# EspHeatController_v1_0_Eagle9x.net
KiCad netlist of a schematic drawn in EAGLE
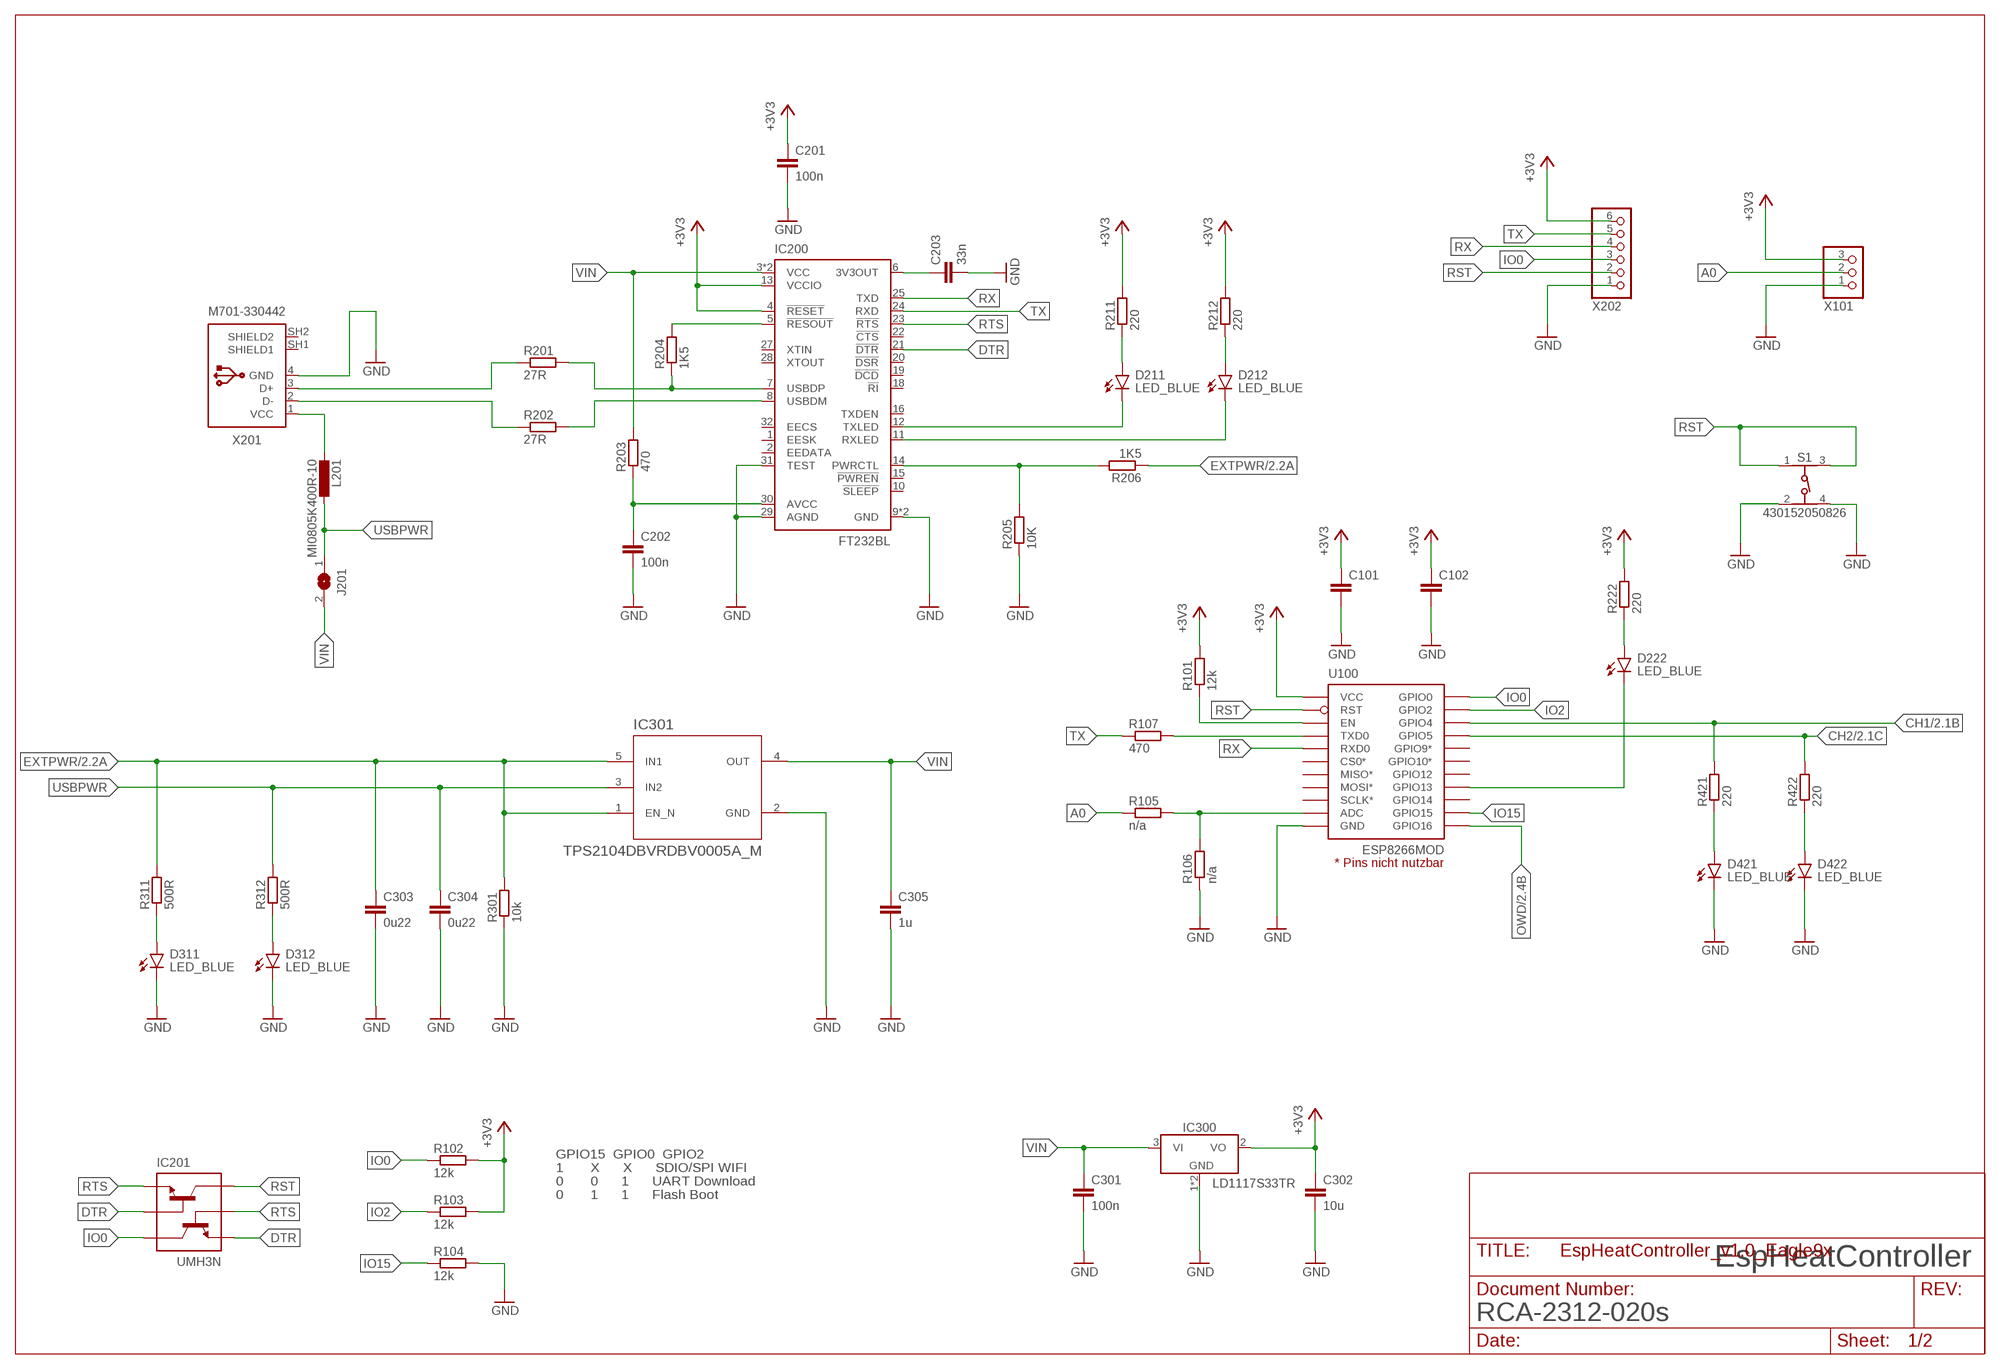
[diagram p0: schematic, sheet 1]
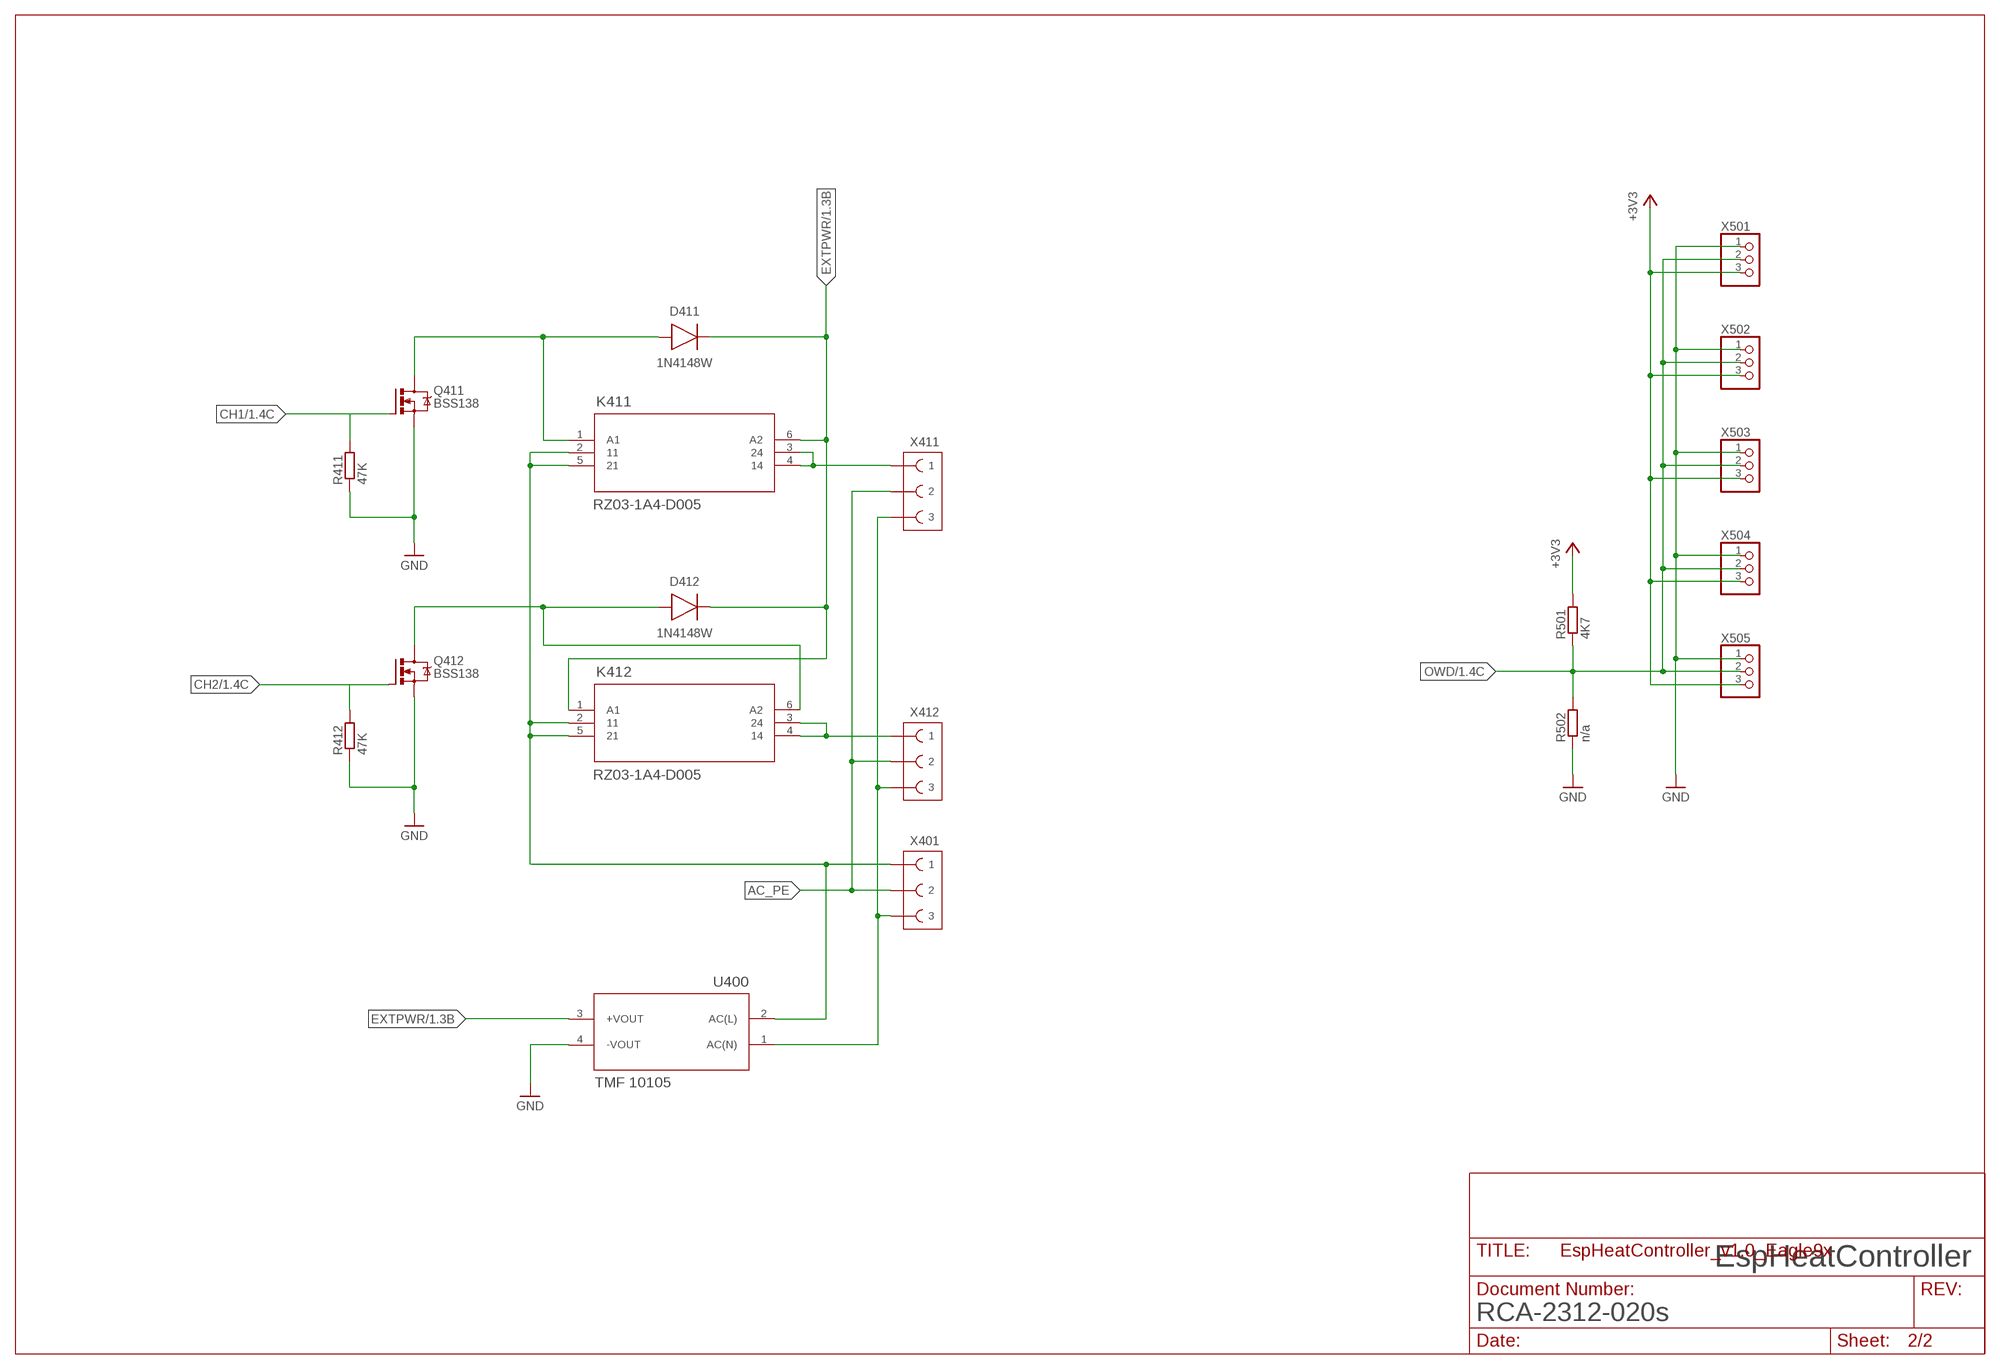
[diagram p1: schematic, sheet 2]

(export (version "E")
  (design (tool "Eeschema 10.0.6"))
  (components
    (comp (ref "C101")
      (value "C-EUC0805")
      (footprint "eagle-import:C0805")
      (libsource (lib "eagle-import") (part "C-EUC0805"))
    )
    (comp (ref "C102")
      (value "C-EUC0805")
      (footprint "eagle-import:C0805")
      (libsource (lib "eagle-import") (part "C-EUC0805"))
    )
    (comp (ref "C201")
      (value "100n")
      (footprint "eagle-import:C0805")
      (libsource (lib "eagle-import") (part "C-EUC0805"))
    )
    (comp (ref "C202")
      (value "100n")
      (footprint "eagle-import:C0805")
      (libsource (lib "eagle-import") (part "C-EUC0805"))
    )
    (comp (ref "C203")
      (value "33n")
      (footprint "eagle-import:C0805")
      (libsource (lib "eagle-import") (part "C-EUC0805"))
    )
    (comp (ref "C301")
      (value "100n")
      (footprint "eagle-import:C0805")
      (libsource (lib "eagle-import") (part "C-EUC0805"))
    )
    (comp (ref "C302")
      (value "10u")
      (footprint "eagle-import:C0805")
      (libsource (lib "eagle-import") (part "C-EUC0805"))
    )
    (comp (ref "C303")
      (value "0u22")
      (footprint "eagle-import:C0805")
      (libsource (lib "eagle-import") (part "C-EUC0805"))
    )
    (comp (ref "C304")
      (value "0u22")
      (footprint "eagle-import:C0805")
      (libsource (lib "eagle-import") (part "C-EUC0805"))
    )
    (comp (ref "C305")
      (value "1u")
      (footprint "eagle-import:C0805")
      (libsource (lib "eagle-import") (part "C-EUC0805"))
    )
    (comp (ref "D211")
      (value "LED_BLUE")
      (footprint "eagle-import:LEDC2012X110N_FLAT-B")
      (libsource (lib "eagle-import") (part "CHIP-FLAT-B_0805"))
    )
    (comp (ref "D212")
      (value "LED_BLUE")
      (footprint "eagle-import:LEDC2012X110N_FLAT-B")
      (libsource (lib "eagle-import") (part "CHIP-FLAT-B_0805"))
    )
    (comp (ref "D222")
      (value "LED_BLUE")
      (footprint "eagle-import:LEDC2012X110N_FLAT-B")
      (libsource (lib "eagle-import") (part "CHIP-FLAT-B_0805"))
    )
    (comp (ref "D311")
      (value "LED_BLUE")
      (footprint "eagle-import:LEDC2012X110N_FLAT-B")
      (libsource (lib "eagle-import") (part "CHIP-FLAT-B_0805"))
    )
    (comp (ref "D312")
      (value "LED_BLUE")
      (footprint "eagle-import:LEDC2012X110N_FLAT-B")
      (libsource (lib "eagle-import") (part "CHIP-FLAT-B_0805"))
    )
    (comp (ref "D421")
      (value "LED_BLUE")
      (footprint "eagle-import:LEDC2012X110N_FLAT-B")
      (libsource (lib "eagle-import") (part "CHIP-FLAT-B_0805"))
    )
    (comp (ref "D422")
      (value "LED_BLUE")
      (footprint "eagle-import:LEDC2012X110N_FLAT-B")
      (libsource (lib "eagle-import") (part "CHIP-FLAT-B_0805"))
    )
    (comp (ref "IC200")
      (value "FT232BL")
      (footprint "eagle-import:LQFP32-7X7")
      (fields (field (name "MF") "FARNELL") (field (name "MPN") "FT232BL/TR"))
      (libsource (lib "eagle-import") (part "FT232BL"))
    )
    (comp (ref "IC201")
      (value "UMH3N")
      (footprint "eagle-import:SOT-363_ROM")
      (fields
        (field (name "MANUFACTURER_PART_NUMBER") "UMH3NTN")
        (field (name "COPYRIGHT") "Copyright (C) 2023 Ultra Librarian. All rights reserved.")
      )
      (libsource (lib "eagle-import") (part "UMH3NTNSOT-363_ROM"))
    )
    (comp (ref "IC300")
      (value "LD1117S33TR")
      (footprint "eagle-import:SOT230P700X170-4")
      (fields (field (name "MANUFACTURER") "STMicroelectronics") (field (name "MPN") "Generic"))
      (libsource (lib "eagle-import") (part "LD1117_SOT223"))
    )
    (comp (ref "IC301")
      (value "TPS2104DBVRDBV0005A_M")
      (footprint "eagle-import:DBV0005A_M")
      (fields
        (field (name "MANUFACTURER_PART_NUMBER") "TPS2104DBVR")
        (field (name "COPYRIGHT") "Copyright (C) 2023 Ultra Librarian. All rights reserved.")
      )
      (libsource (lib "eagle-import") (part "TPS2104DBVRDBV0005A_M"))
    )
    (comp (ref "J201")
      (value "SJ")
      (footprint "eagle-import:SJ")
      (libsource (lib "eagle-import") (part "SJ"))
    )
    (comp (ref "L201")
      (value "MI0805K400R-10")
      (footprint "eagle-import:L2012C")
      (libsource (lib "eagle-import") (part "L-EUL2012C"))
    )
    (comp (ref "R101")
      (value "12k")
      (footprint "eagle-import:R0603")
      (libsource (lib "eagle-import") (part "R-EU_R0603"))
    )
    (comp (ref "R102")
      (value "12k")
      (footprint "eagle-import:R0603")
      (libsource (lib "eagle-import") (part "R-EU_R0603"))
    )
    (comp (ref "R103")
      (value "12k")
      (footprint "eagle-import:R0603")
      (libsource (lib "eagle-import") (part "R-EU_R0603"))
    )
    (comp (ref "R104")
      (value "12k")
      (footprint "eagle-import:R0603")
      (libsource (lib "eagle-import") (part "R-EU_R0603"))
    )
    (comp (ref "R105")
      (value "n/a")
      (footprint "eagle-import:R0603")
      (libsource (lib "eagle-import") (part "R-EU_R0603"))
    )
    (comp (ref "R106")
      (value "n/a")
      (footprint "eagle-import:R0603")
      (libsource (lib "eagle-import") (part "R-EU_R0603"))
    )
    (comp (ref "R107")
      (value "470")
      (footprint "eagle-import:R0603")
      (libsource (lib "eagle-import") (part "R-EU_R0603"))
    )
    (comp (ref "R201")
      (value "27R")
      (footprint "eagle-import:R0603")
      (libsource (lib "eagle-import") (part "R-EU_R0603"))
    )
    (comp (ref "R202")
      (value "27R")
      (footprint "eagle-import:R0603")
      (libsource (lib "eagle-import") (part "R-EU_R0603"))
    )
    (comp (ref "R203")
      (value "470")
      (footprint "eagle-import:R0603")
      (libsource (lib "eagle-import") (part "R-EU_R0603"))
    )
    (comp (ref "R204")
      (value "1K5")
      (footprint "eagle-import:R0603")
      (libsource (lib "eagle-import") (part "R-EU_R0603"))
    )
    (comp (ref "R205")
      (value "10K")
      (footprint "eagle-import:R0603")
      (libsource (lib "eagle-import") (part "R-EU_R0603"))
    )
    (comp (ref "R206")
      (value "1K5")
      (footprint "eagle-import:R0603")
      (libsource (lib "eagle-import") (part "R-EU_R0603"))
    )
    (comp (ref "R211")
      (value "220")
      (footprint "eagle-import:R0603")
      (libsource (lib "eagle-import") (part "R-EU_R0603"))
    )
    (comp (ref "R212")
      (value "220")
      (footprint "eagle-import:R0603")
      (libsource (lib "eagle-import") (part "R-EU_R0603"))
    )
    (comp (ref "R222")
      (value "220")
      (footprint "eagle-import:R0603")
      (libsource (lib "eagle-import") (part "R-EU_R0603"))
    )
    (comp (ref "R301")
      (value "10k")
      (footprint "eagle-import:R0603")
      (libsource (lib "eagle-import") (part "R-EU_R0603"))
    )
    (comp (ref "R311")
      (value "500R")
      (footprint "eagle-import:R0603")
      (libsource (lib "eagle-import") (part "R-EU_R0603"))
    )
    (comp (ref "R312")
      (value "500R")
      (footprint "eagle-import:R0603")
      (libsource (lib "eagle-import") (part "R-EU_R0603"))
    )
    (comp (ref "R421")
      (value "220")
      (footprint "eagle-import:R0603")
      (libsource (lib "eagle-import") (part "R-EU_R0603"))
    )
    (comp (ref "R422")
      (value "220")
      (footprint "eagle-import:R0603")
      (libsource (lib "eagle-import") (part "R-EU_R0603"))
    )
    (comp (ref "S1")
      (value "430152050826")
      (footprint "eagle-import:430152050826")
      (libsource (lib "eagle-import") (part "430152050826"))
    )
    (comp (ref "U100")
      (value "ESP8266MOD")
      (footprint "eagle-import:ESP12F-SMD")
      (libsource (lib "eagle-import") (part "ESP8266MOD"))
    )
    (comp (ref "X101")
      (value "PINHD-1X3")
      (footprint "eagle-import:1X03")
      (libsource (lib "eagle-import") (part "PINHD-1X3"))
    )
    (comp (ref "X201")
      (value "M701-330442")
      (footprint "eagle-import:M701-330442")
      (fields (field (name "MANUFACTURER") "Harwin"))
      (libsource (lib "eagle-import") (part "M701-330442"))
    )
    (comp (ref "X202")
      (value "PINHD-1X6")
      (footprint "eagle-import:1X06")
      (libsource (lib "eagle-import") (part "PINHD-1X6"))
    )
    (comp (ref "D411")
      (value "1N4148W")
      (footprint "eagle-import:SOD3715X135")
      (fields (field (name "MANUFACTURER") "Diodes Incorporated"))
      (libsource (lib "eagle-import") (part "DIODE__SOD123G1N4148W-7-F"))
    )
    (comp (ref "D412")
      (value "1N4148W")
      (footprint "eagle-import:SOD3715X135")
      (fields (field (name "MANUFACTURER") "Diodes Incorporated"))
      (libsource (lib "eagle-import") (part "DIODE__SOD123G1N4148W-7-F"))
    )
    (comp (ref "K411")
      (value "RZ03-1A4-D005")
      (footprint "eagle-import:RELAY-SPST2_5MM")
      (fields
        (field (name "MANUFACTURER_PART_NUMBER") "1-1415899-6")
        (field (name "COPYRIGHT") "Copyright (C) 2016 Accelerated Designs. All rights reserved")
      )
      (libsource (lib "eagle-import") (part "1-1415899-6"))
    )
    (comp (ref "K412")
      (value "RZ03-1A4-D005")
      (footprint "eagle-import:RELAY-SPST2_5MM")
      (fields
        (field (name "MANUFACTURER_PART_NUMBER") "1-1415899-6")
        (field (name "COPYRIGHT") "Copyright (C) 2016 Accelerated Designs. All rights reserved")
      )
      (libsource (lib "eagle-import") (part "1-1415899-6"))
    )
    (comp (ref "Q411")
      (value "BSS138")
      (footprint "eagle-import:SOT23")
      (libsource (lib "eagle-import") (part "NMOSFETSOT23-GSD"))
    )
    (comp (ref "Q412")
      (value "BSS138")
      (footprint "eagle-import:SOT23")
      (libsource (lib "eagle-import") (part "NMOSFETSOT23-GSD"))
    )
    (comp (ref "R411")
      (value "47K")
      (footprint "eagle-import:R0805W")
      (libsource (lib "eagle-import") (part "R-EU_R0805W"))
    )
    (comp (ref "R412")
      (value "47K")
      (footprint "eagle-import:R0805W")
      (libsource (lib "eagle-import") (part "R-EU_R0805W"))
    )
    (comp (ref "R501")
      (value "4K7")
      (footprint "eagle-import:R0805W")
      (libsource (lib "eagle-import") (part "R-EU_R0805W"))
    )
    (comp (ref "R502")
      (value "n/a")
      (footprint "eagle-import:R0805W")
      (libsource (lib "eagle-import") (part "R-EU_R0805W"))
    )
    (comp (ref "U400")
      (value "TMF 10105")
      (footprint "eagle-import:TMF10")
      (libsource (lib "eagle-import") (part "TMF_101"))
    )
    (comp (ref "X401")
      (value "SPT2,5/3-V-5,0")
      (footprint "eagle-import:SPT2,5_3-V-5,0")
      (fields (field (name "ARROW_PART_NUMBER") "1991105") (field (name "MOUSER_PART_NUMBER") "651-1991105"))
      (libsource (lib "eagle-import") (part "SPT2,5/3-V-5,0"))
    )
    (comp (ref "X411")
      (value "SPT2,5/3-V-5,0")
      (footprint "eagle-import:SPT2,5_3-V-5,0")
      (fields (field (name "ARROW_PART_NUMBER") "1991105") (field (name "MOUSER_PART_NUMBER") "651-1991105"))
      (libsource (lib "eagle-import") (part "SPT2,5/3-V-5,0"))
    )
    (comp (ref "X412")
      (value "SPT2,5/3-V-5,0")
      (footprint "eagle-import:SPT2,5_3-V-5,0")
      (fields (field (name "ARROW_PART_NUMBER") "1991105") (field (name "MOUSER_PART_NUMBER") "651-1991105"))
      (libsource (lib "eagle-import") (part "SPT2,5/3-V-5,0"))
    )
    (comp (ref "X501")
      (value "PINHD-1X3")
      (footprint "eagle-import:1X03")
      (libsource (lib "eagle-import") (part "PINHD-1X3"))
    )
    (comp (ref "X502")
      (value "PINHD-1X3")
      (footprint "eagle-import:1X03")
      (libsource (lib "eagle-import") (part "PINHD-1X3"))
    )
    (comp (ref "X503")
      (value "PINHD-1X3")
      (footprint "eagle-import:1X03")
      (libsource (lib "eagle-import") (part "PINHD-1X3"))
    )
    (comp (ref "X504")
      (value "PINHD-1X3")
      (footprint "eagle-import:1X03")
      (libsource (lib "eagle-import") (part "PINHD-1X3"))
    )
    (comp (ref "X505")
      (value "PINHD-1X3")
      (footprint "eagle-import:1X03")
      (libsource (lib "eagle-import") (part "PINHD-1X3"))
    )
  )
  (nets
    (net (code "1") (name "+3V3") (class "Default")
      (node (ref "C101") (pin "1") (pinfunction "1_1") (pintype "passive"))
      (node (ref "C102") (pin "1") (pinfunction "1_1") (pintype "passive"))
      (node (ref "C201") (pin "1") (pinfunction "1_1") (pintype "passive"))
      (node (ref "C302") (pin "1") (pinfunction "1_1") (pintype "passive"))
      (node (ref "IC200") (pin "13") (pinfunction "VCCIO_13") (pintype "power_in"))
      (node (ref "IC200") (pin "4") (pinfunction "~{RESET}_4") (pintype "input"))
      (node (ref "IC300") (pin "2") (pinfunction "VO_2") (pintype "output"))
      (node (ref "R101") (pin "2") (pinfunction "2_2") (pintype "passive"))
      (node (ref "R102") (pin "2") (pinfunction "2_2") (pintype "passive"))
      (node (ref "R103") (pin "2") (pinfunction "2_2") (pintype "passive"))
      (node (ref "R211") (pin "2") (pinfunction "2_2") (pintype "passive"))
      (node (ref "R212") (pin "2") (pinfunction "2_2") (pintype "passive"))
      (node (ref "R222") (pin "2") (pinfunction "2_2") (pintype "passive"))
      (node (ref "R501") (pin "2") (pinfunction "2_2") (pintype "passive"))
      (node (ref "U100") (pin "VCC") (pinfunction "VCC_VCC") (pintype "bidirectional"))
      (node (ref "X101") (pin "3") (pinfunction "3_3") (pintype "passive"))
      (node (ref "X202") (pin "6") (pinfunction "6_6") (pintype "passive"))
      (node (ref "X501") (pin "3") (pinfunction "3_3") (pintype "passive"))
      (node (ref "X502") (pin "3") (pinfunction "3_3") (pintype "passive"))
      (node (ref "X503") (pin "3") (pinfunction "3_3") (pintype "passive"))
      (node (ref "X504") (pin "3") (pinfunction "3_3") (pintype "passive"))
      (node (ref "X505") (pin "3") (pinfunction "3_3") (pintype "passive"))
    )
    (net (code "2") (name "A0") (class "Default")
      (node (ref "R105") (pin "1") (pinfunction "1_1") (pintype "passive"))
      (node (ref "X101") (pin "2") (pinfunction "2_2") (pintype "passive"))
    )
    (net (code "3") (name "AC_PE") (class "Default")
      (node (ref "X401") (pin "2A") (pinfunction "2_2A") (pintype "bidirectional"))
      (node (ref "X401") (pin "2B") (pinfunction "2_2B") (pintype "bidirectional"))
      (node (ref "X411") (pin "2A") (pinfunction "2_2A") (pintype "bidirectional"))
      (node (ref "X411") (pin "2B") (pinfunction "2_2B") (pintype "bidirectional"))
      (node (ref "X412") (pin "2A") (pinfunction "2_2A") (pintype "bidirectional"))
      (node (ref "X412") (pin "2B") (pinfunction "2_2B") (pintype "bidirectional"))
    )
    (net (code "4") (name "CH1") (class "Default")
      (node (ref "Q411") (pin "1") (pinfunction "G_1") (pintype "passive"))
      (node (ref "R411") (pin "2") (pinfunction "2_2") (pintype "passive"))
      (node (ref "R421") (pin "2") (pinfunction "2_2") (pintype "passive"))
      (node (ref "U100") (pin "GPIO4") (pinfunction "GPIO4_GPIO4") (pintype "bidirectional"))
    )
    (net (code "5") (name "CH2") (class "Default")
      (node (ref "Q412") (pin "1") (pinfunction "G_1") (pintype "passive"))
      (node (ref "R412") (pin "2") (pinfunction "2_2") (pintype "passive"))
      (node (ref "R422") (pin "2") (pinfunction "2_2") (pintype "passive"))
      (node (ref "U100") (pin "GPIO5") (pinfunction "GPIO5_GPIO5") (pintype "bidirectional"))
    )
    (net (code "6") (name "DTR") (class "Default")
      (node (ref "IC200") (pin "21") (pinfunction "~{DTR}_21") (pintype "output"))
      (node (ref "IC201") (pin "2") (pinfunction "B1_2") (pintype "passive"))
      (node (ref "IC201") (pin "4") (pinfunction "E2_4") (pintype "passive"))
    )
    (net (code "7") (name "EXTPWR") (class "Default")
      (node (ref "C303") (pin "1") (pinfunction "1_1") (pintype "passive"))
      (node (ref "D411") (pin "1") (pinfunction "C_1") (pintype "passive"))
      (node (ref "D412") (pin "1") (pinfunction "C_1") (pintype "passive"))
      (node (ref "IC301") (pin "1") (pinfunction "EN_N_1") (pintype "input"))
      (node (ref "IC301") (pin "5") (pinfunction "IN1_5") (pintype "input"))
      (node (ref "K411") (pin "6") (pinfunction "A2_6") (pintype "passive"))
      (node (ref "K412") (pin "1") (pinfunction "A1_1") (pintype "passive"))
      (node (ref "R206") (pin "1") (pinfunction "1_1") (pintype "passive"))
      (node (ref "R301") (pin "2") (pinfunction "2_2") (pintype "passive"))
      (node (ref "R311") (pin "2") (pinfunction "2_2") (pintype "passive"))
      (node (ref "U400") (pin "3") (pinfunction "+VOUT_3") (pintype "power_in"))
    )
    (net (code "8") (name "GND") (class "Default")
      (node (ref "C101") (pin "2") (pinfunction "2_2") (pintype "passive"))
      (node (ref "C102") (pin "2") (pinfunction "2_2") (pintype "passive"))
      (node (ref "C201") (pin "2") (pinfunction "2_2") (pintype "passive"))
      (node (ref "C202") (pin "2") (pinfunction "2_2") (pintype "passive"))
      (node (ref "C203") (pin "2") (pinfunction "2_2") (pintype "passive"))
      (node (ref "C301") (pin "2") (pinfunction "2_2") (pintype "passive"))
      (node (ref "C302") (pin "2") (pinfunction "2_2") (pintype "passive"))
      (node (ref "C303") (pin "2") (pinfunction "2_2") (pintype "passive"))
      (node (ref "C304") (pin "2") (pinfunction "2_2") (pintype "passive"))
      (node (ref "C305") (pin "2") (pinfunction "2_2") (pintype "passive"))
      (node (ref "D311") (pin "C") (pinfunction "C_C") (pintype "passive"))
      (node (ref "D312") (pin "C") (pinfunction "C_C") (pintype "passive"))
      (node (ref "D421") (pin "C") (pinfunction "C_C") (pintype "passive"))
      (node (ref "D422") (pin "C") (pinfunction "C_C") (pintype "passive"))
      (node (ref "IC200") (pin "17") (pinfunction "GND_17") (pintype "power_in"))
      (node (ref "IC200") (pin "29") (pinfunction "AGND_29") (pintype "power_in"))
      (node (ref "IC200") (pin "31") (pinfunction "TEST_31") (pintype "input"))
      (node (ref "IC200") (pin "9") (pinfunction "GND_9") (pintype "power_in"))
      (node (ref "IC300") (pin "1") (pinfunction "GND_1") (pintype "passive"))
      (node (ref "IC300") (pin "4") (pinfunction "GND_4") (pintype "passive"))
      (node (ref "IC301") (pin "2") (pinfunction "GND_2") (pintype "power_in"))
      (node (ref "Q411") (pin "2") (pinfunction "S_2") (pintype "passive"))
      (node (ref "Q412") (pin "2") (pinfunction "S_2") (pintype "passive"))
      (node (ref "R104") (pin "2") (pinfunction "2_2") (pintype "passive"))
      (node (ref "R106") (pin "1") (pinfunction "1_1") (pintype "passive"))
      (node (ref "R205") (pin "1") (pinfunction "1_1") (pintype "passive"))
      (node (ref "R301") (pin "1") (pinfunction "1_1") (pintype "passive"))
      (node (ref "R411") (pin "1") (pinfunction "1_1") (pintype "passive"))
      (node (ref "R412") (pin "1") (pinfunction "1_1") (pintype "passive"))
      (node (ref "R502") (pin "1") (pinfunction "1_1") (pintype "passive"))
      (node (ref "S1") (pin "2") (pinfunction "2_2") (pintype "passive"))
      (node (ref "S1") (pin "4") (pinfunction "4_4") (pintype "passive"))
      (node (ref "U100") (pin "GND") (pinfunction "GND_GND") (pintype "bidirectional"))
      (node (ref "U400") (pin "4") (pinfunction "-VOUT_4") (pintype "power_in"))
      (node (ref "X101") (pin "1") (pinfunction "1_1") (pintype "passive"))
      (node (ref "X201") (pin "4") (pinfunction "GND_4") (pintype "power_in"))
      (node (ref "X202") (pin "1") (pinfunction "1_1") (pintype "passive"))
      (node (ref "X501") (pin "1") (pinfunction "1_1") (pintype "passive"))
      (node (ref "X502") (pin "1") (pinfunction "1_1") (pintype "passive"))
      (node (ref "X503") (pin "1") (pinfunction "1_1") (pintype "passive"))
      (node (ref "X504") (pin "1") (pinfunction "1_1") (pintype "passive"))
      (node (ref "X505") (pin "1") (pinfunction "1_1") (pintype "passive"))
    )
    (net (code "9") (name "IO0") (class "Default")
      (node (ref "IC201") (pin "3") (pinfunction "C2_3") (pintype "passive"))
      (node (ref "R102") (pin "1") (pinfunction "1_1") (pintype "passive"))
      (node (ref "U100") (pin "GPIO0") (pinfunction "GPIO0_GPIO0") (pintype "bidirectional"))
      (node (ref "X202") (pin "3") (pinfunction "3_3") (pintype "passive"))
    )
    (net (code "10") (name "IO2") (class "Default")
      (node (ref "R103") (pin "1") (pinfunction "1_1") (pintype "passive"))
      (node (ref "U100") (pin "GPIO2") (pinfunction "GPIO2_GPIO2") (pintype "bidirectional"))
    )
    (net (code "11") (name "IO15") (class "Default")
      (node (ref "R104") (pin "1") (pinfunction "1_1") (pintype "passive"))
      (node (ref "U100") (pin "GPIO15") (pinfunction "GPIO15_GPIO15") (pintype "bidirectional"))
    )
    (net (code "12") (name "Net-(D211-PadA)") (class "Default")
      (node (ref "D211") (pin "A") (pinfunction "A_A") (pintype "passive"))
      (node (ref "R211") (pin "1") (pinfunction "1_1") (pintype "passive"))
    )
    (net (code "13") (name "Net-(D212-PadA)") (class "Default")
      (node (ref "D212") (pin "A") (pinfunction "A_A") (pintype "passive"))
      (node (ref "R212") (pin "1") (pinfunction "1_1") (pintype "passive"))
    )
    (net (code "14") (name "Net-(D222-PadA)") (class "Default")
      (node (ref "D222") (pin "A") (pinfunction "A_A") (pintype "passive"))
      (node (ref "R222") (pin "1") (pinfunction "1_1") (pintype "passive"))
    )
    (net (code "15") (name "Net-(D222-PadC)") (class "Default")
      (node (ref "D222") (pin "C") (pinfunction "C_C") (pintype "passive"))
      (node (ref "U100") (pin "GPIO13") (pinfunction "GPIO13_GPIO13") (pintype "bidirectional"))
    )
    (net (code "16") (name "Net-(D311-PadA)") (class "Default")
      (node (ref "D311") (pin "A") (pinfunction "A_A") (pintype "passive"))
      (node (ref "R311") (pin "1") (pinfunction "1_1") (pintype "passive"))
    )
    (net (code "17") (name "Net-(D312-PadA)") (class "Default")
      (node (ref "D312") (pin "A") (pinfunction "A_A") (pintype "passive"))
      (node (ref "R312") (pin "1") (pinfunction "1_1") (pintype "passive"))
    )
    (net (code "18") (name "Net-(D411-A)") (class "Default")
      (node (ref "D411") (pin "2") (pinfunction "A_2") (pintype "passive"))
      (node (ref "K411") (pin "1") (pinfunction "A1_1") (pintype "passive"))
      (node (ref "Q411") (pin "3") (pinfunction "D_3") (pintype "passive"))
    )
    (net (code "19") (name "Net-(D412-A)") (class "Default")
      (node (ref "D412") (pin "2") (pinfunction "A_2") (pintype "passive"))
      (node (ref "K412") (pin "6") (pinfunction "A2_6") (pintype "passive"))
      (node (ref "Q412") (pin "3") (pinfunction "D_3") (pintype "passive"))
    )
    (net (code "20") (name "Net-(D421-PadA)") (class "Default")
      (node (ref "D421") (pin "A") (pinfunction "A_A") (pintype "passive"))
      (node (ref "R421") (pin "1") (pinfunction "1_1") (pintype "passive"))
    )
    (net (code "21") (name "Net-(D422-PadA)") (class "Default")
      (node (ref "D422") (pin "A") (pinfunction "A_A") (pintype "passive"))
      (node (ref "R422") (pin "1") (pinfunction "1_1") (pintype "passive"))
    )
    (net (code "22") (name "Net-(IC200-3V3OUT)") (class "Default")
      (node (ref "C203") (pin "1") (pinfunction "1_1") (pintype "passive"))
      (node (ref "IC200") (pin "6") (pinfunction "3V3OUT_6") (pintype "output"))
    )
    (net (code "23") (name "Net-(IC200-AVCC)") (class "Default")
      (node (ref "C202") (pin "1") (pinfunction "1_1") (pintype "passive"))
      (node (ref "IC200") (pin "30") (pinfunction "AVCC_30") (pintype "power_in"))
      (node (ref "R203") (pin "1") (pinfunction "1_1") (pintype "passive"))
    )
    (net (code "24") (name "Net-(IC200-PWRCTL)") (class "Default")
      (node (ref "IC200") (pin "14") (pinfunction "PWRCTL_14") (pintype "bidirectional"))
      (node (ref "R205") (pin "2") (pinfunction "2_2") (pintype "passive"))
      (node (ref "R206") (pin "2") (pinfunction "2_2") (pintype "passive"))
    )
    (net (code "25") (name "Net-(IC200-RXLED)") (class "Default")
      (node (ref "D212") (pin "C") (pinfunction "C_C") (pintype "passive"))
      (node (ref "IC200") (pin "11") (pinfunction "RXLED_11") (pintype "bidirectional"))
    )
    (net (code "26") (name "Net-(IC200-TXLED)") (class "Default")
      (node (ref "D211") (pin "C") (pinfunction "C_C") (pintype "passive"))
      (node (ref "IC200") (pin "12") (pinfunction "TXLED_12") (pintype "bidirectional"))
    )
    (net (code "27") (name "Net-(IC200-USBDM)") (class "Default")
      (node (ref "IC200") (pin "8") (pinfunction "USBDM_8") (pintype "bidirectional"))
      (node (ref "R202") (pin "2") (pinfunction "2_2") (pintype "passive"))
    )
    (net (code "28") (name "Net-(IC200-USBDP)") (class "Default")
      (node (ref "IC200") (pin "7") (pinfunction "USBDP_7") (pintype "bidirectional"))
      (node (ref "R201") (pin "2") (pinfunction "2_2") (pintype "passive"))
      (node (ref "R204") (pin "1") (pinfunction "1_1") (pintype "passive"))
    )
    (net (code "29") (name "Net-(IC200-~{RESOUT})") (class "Default")
      (node (ref "IC200") (pin "5") (pinfunction "~{RESOUT}_5") (pintype "input"))
      (node (ref "R204") (pin "2") (pinfunction "2_2") (pintype "passive"))
    )
    (net (code "30") (name "Net-(K411-11)") (class "Default")
      (node (ref "K411") (pin "2") (pinfunction "11_2") (pintype "passive"))
      (node (ref "K411") (pin "5") (pinfunction "21_5") (pintype "passive"))
      (node (ref "K412") (pin "2") (pinfunction "11_2") (pintype "passive"))
      (node (ref "K412") (pin "5") (pinfunction "21_5") (pintype "passive"))
      (node (ref "U400") (pin "2") (pinfunction "AC(L)_2") (pintype "passive"))
      (node (ref "X401") (pin "1A") (pinfunction "1_1A") (pintype "bidirectional"))
      (node (ref "X401") (pin "1B") (pinfunction "1_1B") (pintype "bidirectional"))
    )
    (net (code "31") (name "Net-(K411-14)") (class "Default")
      (node (ref "K411") (pin "3") (pinfunction "24_3") (pintype "passive"))
      (node (ref "K411") (pin "4") (pinfunction "14_4") (pintype "passive"))
      (node (ref "X411") (pin "1A") (pinfunction "1_1A") (pintype "bidirectional"))
      (node (ref "X411") (pin "1B") (pinfunction "1_1B") (pintype "bidirectional"))
    )
    (net (code "32") (name "Net-(K412-14)") (class "Default")
      (node (ref "K412") (pin "3") (pinfunction "24_3") (pintype "passive"))
      (node (ref "K412") (pin "4") (pinfunction "14_4") (pintype "passive"))
      (node (ref "X412") (pin "1A") (pinfunction "1_1A") (pintype "bidirectional"))
      (node (ref "X412") (pin "1B") (pinfunction "1_1B") (pintype "bidirectional"))
    )
    (net (code "33") (name "Net-(R101-Pad1)") (class "Default")
      (node (ref "R101") (pin "1") (pinfunction "1_1") (pintype "passive"))
      (node (ref "U100") (pin "EN") (pinfunction "EN_EN") (pintype "bidirectional"))
    )
    (net (code "34") (name "Net-(R105-Pad2)") (class "Default")
      (node (ref "R105") (pin "2") (pinfunction "2_2") (pintype "passive"))
      (node (ref "R106") (pin "2") (pinfunction "2_2") (pintype "passive"))
      (node (ref "U100") (pin "ADC") (pinfunction "ADC_ADC") (pintype "bidirectional"))
    )
    (net (code "35") (name "Net-(R107-Pad2)") (class "Default")
      (node (ref "R107") (pin "2") (pinfunction "2_2") (pintype "passive"))
      (node (ref "U100") (pin "TXD0") (pinfunction "TXD0_TXD0") (pintype "bidirectional"))
    )
    (net (code "36") (name "Net-(U400-AC(N))") (class "Default")
      (node (ref "U400") (pin "1") (pinfunction "AC(N)_1") (pintype "passive"))
      (node (ref "X401") (pin "3A") (pinfunction "3_3A") (pintype "bidirectional"))
      (node (ref "X401") (pin "3B") (pinfunction "3_3B") (pintype "bidirectional"))
      (node (ref "X411") (pin "3A") (pinfunction "3_3A") (pintype "bidirectional"))
      (node (ref "X411") (pin "3B") (pinfunction "3_3B") (pintype "bidirectional"))
      (node (ref "X412") (pin "3A") (pinfunction "3_3A") (pintype "bidirectional"))
      (node (ref "X412") (pin "3B") (pinfunction "3_3B") (pintype "bidirectional"))
    )
    (net (code "37") (name "Net-(X201-D+)") (class "Default")
      (node (ref "R201") (pin "1") (pinfunction "1_1") (pintype "passive"))
      (node (ref "X201") (pin "3") (pinfunction "D+_3") (pintype "bidirectional"))
    )
    (net (code "38") (name "Net-(X201-D-)") (class "Default")
      (node (ref "R202") (pin "1") (pinfunction "1_1") (pintype "passive"))
      (node (ref "X201") (pin "2") (pinfunction "D-_2") (pintype "bidirectional"))
    )
    (net (code "39") (name "Net-(X201-VCC)") (class "Default")
      (node (ref "L201") (pin "2") (pinfunction "2_2") (pintype "passive"))
      (node (ref "X201") (pin "1") (pinfunction "VCC_1") (pintype "power_in"))
    )
    (net (code "40") (name "OWD") (class "Default")
      (node (ref "R501") (pin "1") (pinfunction "1_1") (pintype "passive"))
      (node (ref "R502") (pin "2") (pinfunction "2_2") (pintype "passive"))
      (node (ref "U100") (pin "GPIO16") (pinfunction "GPIO16_GPIO16") (pintype "bidirectional"))
      (node (ref "X501") (pin "2") (pinfunction "2_2") (pintype "passive"))
      (node (ref "X502") (pin "2") (pinfunction "2_2") (pintype "passive"))
      (node (ref "X503") (pin "2") (pinfunction "2_2") (pintype "passive"))
      (node (ref "X504") (pin "2") (pinfunction "2_2") (pintype "passive"))
      (node (ref "X505") (pin "2") (pinfunction "2_2") (pintype "passive"))
    )
    (net (code "41") (name "RST") (class "Default")
      (node (ref "IC201") (pin "6") (pinfunction "C1_6") (pintype "passive"))
      (node (ref "S1") (pin "1") (pinfunction "1_1") (pintype "passive"))
      (node (ref "S1") (pin "3") (pinfunction "3_3") (pintype "passive"))
      (node (ref "U100") (pin "RST") (pinfunction "RST_RST") (pintype "bidirectional"))
      (node (ref "X202") (pin "2") (pinfunction "2_2") (pintype "passive"))
    )
    (net (code "42") (name "RTS") (class "Default")
      (node (ref "IC200") (pin "23") (pinfunction "~{RTS}_23") (pintype "output"))
      (node (ref "IC201") (pin "1") (pinfunction "E1_1") (pintype "passive"))
      (node (ref "IC201") (pin "5") (pinfunction "B2_5") (pintype "passive"))
    )
    (net (code "43") (name "RX") (class "Default")
      (node (ref "IC200") (pin "25") (pinfunction "TXD_25") (pintype "output"))
      (node (ref "U100") (pin "RXD0") (pinfunction "RXD0_RXD0") (pintype "bidirectional"))
      (node (ref "X202") (pin "4") (pinfunction "4_4") (pintype "passive"))
    )
    (net (code "44") (name "SHIELD1") (class "Default")
      (node (ref "X201") (pin "SH1") (pinfunction "SHIELD1_SH1") (pintype "power_in"))
    )
    (net (code "45") (name "SHIELD2") (class "Default")
      (node (ref "X201") (pin "SH2") (pinfunction "SHIELD2_SH2") (pintype "power_in"))
    )
    (net (code "46") (name "TX") (class "Default")
      (node (ref "IC200") (pin "24") (pinfunction "RXD_24") (pintype "input"))
      (node (ref "R107") (pin "1") (pinfunction "1_1") (pintype "passive"))
      (node (ref "X202") (pin "5") (pinfunction "5_5") (pintype "passive"))
    )
    (net (code "47") (name "USBPWR") (class "Default")
      (node (ref "C304") (pin "1") (pinfunction "1_1") (pintype "passive"))
      (node (ref "IC301") (pin "3") (pinfunction "IN2_3") (pintype "input"))
      (node (ref "J201") (pin "1") (pinfunction "1_1") (pintype "passive"))
      (node (ref "L201") (pin "1") (pinfunction "1_1") (pintype "passive"))
      (node (ref "R312") (pin "2") (pinfunction "2_2") (pintype "passive"))
    )
    (net (code "48") (name "VIN") (class "Default")
      (node (ref "C301") (pin "1") (pinfunction "1_1") (pintype "passive"))
      (node (ref "C305") (pin "1") (pinfunction "1_1") (pintype "passive"))
      (node (ref "IC200") (pin "26") (pinfunction "VCC_26") (pintype "power_in"))
      (node (ref "IC200") (pin "3") (pinfunction "VCC_3") (pintype "power_in"))
      (node (ref "IC300") (pin "3") (pinfunction "VI_3") (pintype "input"))
      (node (ref "IC301") (pin "4") (pinfunction "OUT_4") (pintype "output"))
      (node (ref "J201") (pin "2") (pinfunction "2_2") (pintype "passive"))
      (node (ref "R203") (pin "2") (pinfunction "2_2") (pintype "passive"))
    )
    (net (code "49") (name "unconnected-(IC200-EECS-Pad32)") (class "Default")
      (node (ref "IC200") (pin "32") (pinfunction "EECS_32") (pintype "input"))
    )
    (net (code "50") (name "unconnected-(IC200-EEDATA-Pad2)") (class "Default")
      (node (ref "IC200") (pin "2") (pinfunction "EEDATA_2") (pintype "input"))
    )
    (net (code "51") (name "unconnected-(IC200-EESK-Pad1)") (class "Default")
      (node (ref "IC200") (pin "1") (pinfunction "EESK_1") (pintype "input"))
    )
    (net (code "52") (name "unconnected-(IC200-TXDEN-Pad16)") (class "Default")
      (node (ref "IC200") (pin "16") (pinfunction "TXDEN_16") (pintype "bidirectional"))
    )
    (net (code "53") (name "unconnected-(IC200-XTIN-Pad27)") (class "Default")
      (node (ref "IC200") (pin "27") (pinfunction "XTIN_27") (pintype "input"))
    )
    (net (code "54") (name "unconnected-(IC200-XTOUT-Pad28)") (class "Default")
      (node (ref "IC200") (pin "28") (pinfunction "XTOUT_28") (pintype "output"))
    )
    (net (code "55") (name "unconnected-(IC200-~{CTS}-Pad22)") (class "Default")
      (node (ref "IC200") (pin "22") (pinfunction "~{CTS}_22") (pintype "input"))
    )
    (net (code "56") (name "unconnected-(IC200-~{DCD}-Pad19)") (class "Default")
      (node (ref "IC200") (pin "19") (pinfunction "~{DCD}_19") (pintype "input"))
    )
    (net (code "57") (name "unconnected-(IC200-~{DSR}-Pad20)") (class "Default")
      (node (ref "IC200") (pin "20") (pinfunction "~{DSR}_20") (pintype "input"))
    )
    (net (code "58") (name "unconnected-(IC200-~{PWREN}-Pad15)") (class "Default")
      (node (ref "IC200") (pin "15") (pinfunction "~{PWREN}_15") (pintype "bidirectional"))
    )
    (net (code "59") (name "unconnected-(IC200-~{RI}-Pad18)") (class "Default")
      (node (ref "IC200") (pin "18") (pinfunction "~{RI}_18") (pintype "input"))
    )
    (net (code "60") (name "unconnected-(IC200-~{SLEEP}-Pad10)") (class "Default")
      (node (ref "IC200") (pin "10") (pinfunction "~{SLEEP}_10") (pintype "input"))
    )
    (net (code "61") (name "unconnected-(U100-CS0*-PadCS0)") (class "Default")
      (node (ref "U100") (pin "CS0") (pinfunction "CS0*_CS0") (pintype "bidirectional"))
    )
    (net (code "62") (name "unconnected-(U100-GPIO9*-PadGPIO9)") (class "Default")
      (node (ref "U100") (pin "GPIO9") (pinfunction "GPIO9*_GPIO9") (pintype "bidirectional"))
    )
    (net (code "63") (name "unconnected-(U100-GPIO10*-PadGPIO10)") (class "Default")
      (node (ref "U100") (pin "GPIO10") (pinfunction "GPIO10*_GPIO10") (pintype "bidirectional"))
    )
    (net (code "64") (name "unconnected-(U100-MISO*-PadMISO)") (class "Default")
      (node (ref "U100") (pin "MISO") (pinfunction "MISO*_MISO") (pintype "bidirectional"))
    )
    (net (code "65") (name "unconnected-(U100-MOSI*-PadMOSI)") (class "Default")
      (node (ref "U100") (pin "MOSI") (pinfunction "MOSI*_MOSI") (pintype "bidirectional"))
    )
    (net (code "66") (name "unconnected-(U100-PadGPIO12)") (class "Default")
      (node (ref "U100") (pin "GPIO12") (pinfunction "GPIO12_GPIO12") (pintype "bidirectional"))
    )
    (net (code "67") (name "unconnected-(U100-PadGPIO14)") (class "Default")
      (node (ref "U100") (pin "GPIO14") (pinfunction "GPIO14_GPIO14") (pintype "bidirectional"))
    )
    (net (code "68") (name "unconnected-(U100-SCLK*-PadSCLK)") (class "Default")
      (node (ref "U100") (pin "SCLK") (pinfunction "SCLK*_SCLK") (pintype "bidirectional"))
    )
  )
)
